# v0_2.net
KiCad netlist of a schematic drawn in EAGLE
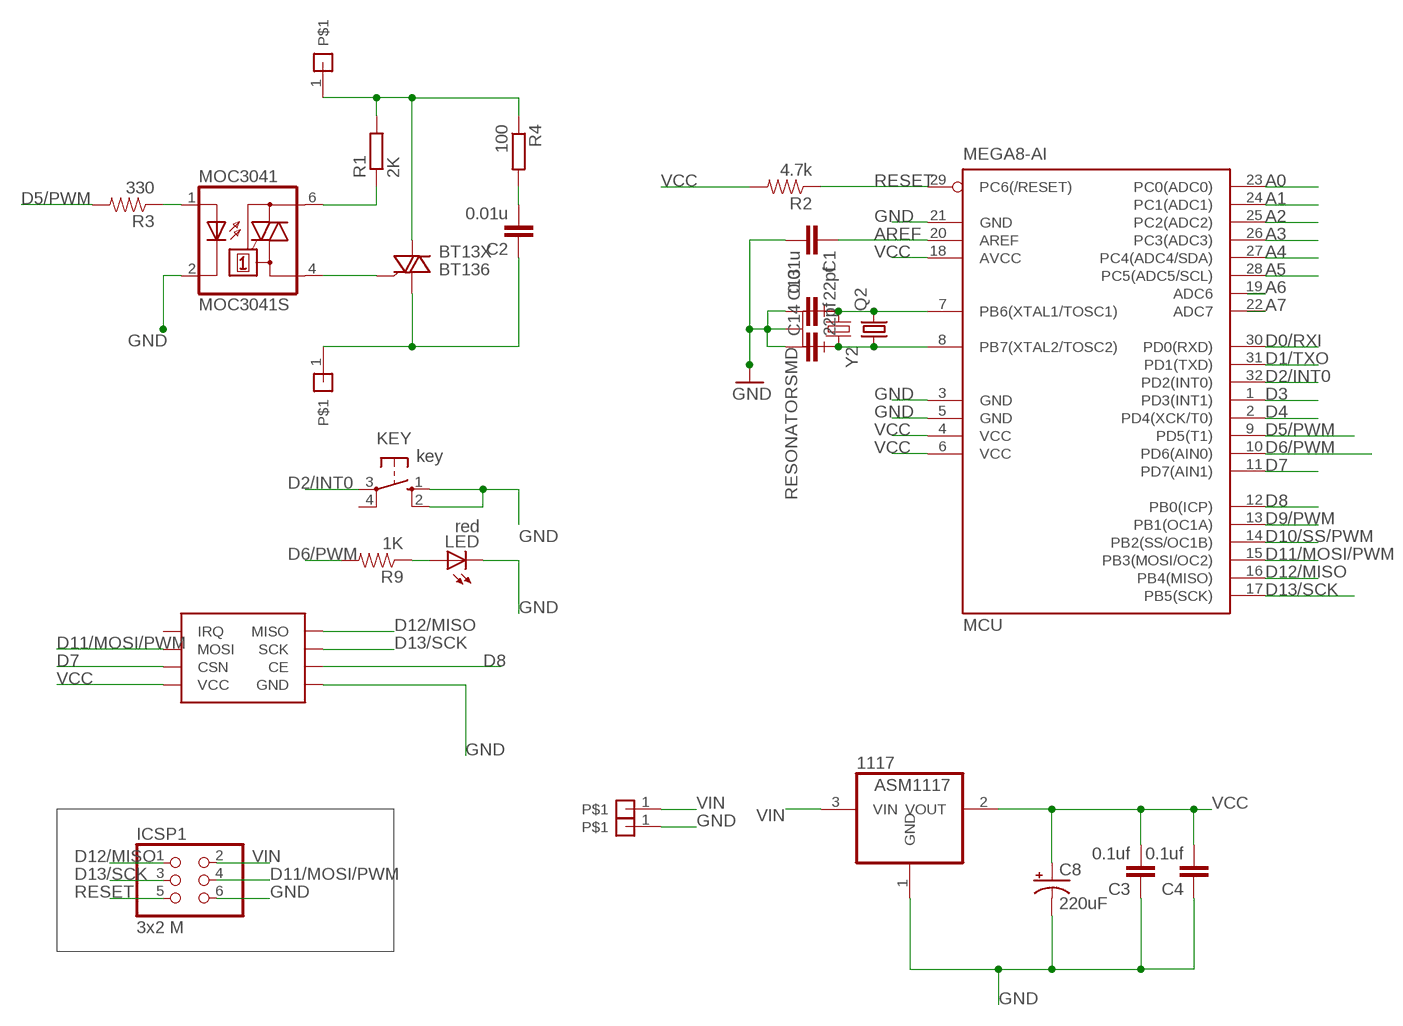
[diagram p0: schematic, sheet 1]

(export (version "E")
  (design (tool "Eeschema 10.0.6"))
  (components
    (comp (ref "1117")
      (value "ASM1117")
      (footprint "eagle-import:SOT223")
      (fields (field (name "MPN") "REG1117"))
      (libsource (lib "eagle-import") (part "REG1117"))
    )
    (comp (ref "BT13X")
      (value "BT136")
      (footprint "eagle-import:TO252")
      (libsource (lib "eagle-import") (part "BT136"))
    )
    (comp (ref "C1")
      (value "0.01u")
      (footprint "eagle-import:0603-CAP")
      (libsource (lib "eagle-import") (part "MY2_CAP0603-CAP"))
    )
    (comp (ref "C2")
      (value "0.01u")
      (footprint "eagle-import:C050-024X044")
      (libsource (lib "eagle-import") (part "C-EU050-024X044"))
    )
    (comp (ref "C3")
      (value "0.1uf")
      (footprint "eagle-import:0603-CAP")
      (libsource (lib "eagle-import") (part "MY_CAP0603-CAP"))
    )
    (comp (ref "C4")
      (value "0.1uf")
      (footprint "eagle-import:0603-CAP")
      (libsource (lib "eagle-import") (part "MY_CAP0603-CAP"))
    )
    (comp (ref "C8")
      (value "220uF")
      (footprint "eagle-import:EIA3528")
      (libsource (lib "eagle-import") (part "CAP_POL3528"))
    )
    (comp (ref "C13")
      (value "22pf")
      (footprint "eagle-import:0603-CAP")
      (libsource (lib "eagle-import") (part "CAP0603-CAP"))
    )
    (comp (ref "C14")
      (value "22pf")
      (footprint "eagle-import:0603-CAP")
      (libsource (lib "eagle-import") (part "CAP0603-CAP"))
    )
    (comp (ref "ICSP1")
      (value "3x2 M")
      (footprint "eagle-import:2X03")
      (libsource (lib "eagle-import") (part "PINHD-2X3"))
    )
    (comp (ref "KEY")
      (value "key")
      (footprint "eagle-import:B3F-10XX")
      (fields
        (field (name "MPN") "B3F-1000")
        (field (name "MPN_1") "B3F-1000")
        (field (name "OC_FARNELL") "176432")
        (field (name "OC_NEWARK") "36M3542")
      )
      (libsource (lib "eagle-import") (part "10-XX"))
    )
    (comp (ref "LED")
      (value "red")
      (footprint "eagle-import:LED3MM")
      (libsource (lib "eagle-import") (part "LED3MM"))
    )
    (comp (ref "MCU")
      (value "MEGA8-AI")
      (footprint "eagle-import:TQFP32-08")
      (fields (field (name "MPN") "ATMEGA8-16AU"))
      (libsource (lib "eagle-import") (part "MEGA8-AI"))
    )
    (comp (ref "MOC3041")
      (value "MOC3041S")
      (footprint "eagle-import:DIL6-SMD")
      (fields
        (field (name "MF") "FAIRCHILD SEMICONDUCTOR")
        (field (name "MPN") "MOC3041S-M")
        (field (name "MF_1") "FAIRCHILD SEMICONDUCTOR")
        (field (name "MPN_1") "MOC3041S-M")
        (field (name "OC_NEWARK") "05C2885")
      )
      (libsource (lib "eagle-import") (part "MOC30S41"))
    )
    (comp (ref "Q2")
      (value "CRYSTALHC49S")
      (footprint "eagle-import:HC49_S")
      (libsource (lib "eagle-import") (part "CRYSTALHC49S"))
    )
    (comp (ref "R1")
      (value "2K")
      (footprint "eagle-import:0204_7")
      (libsource (lib "eagle-import") (part "R-EU_0204/7"))
    )
    (comp (ref "R2")
      (value "4.7k")
      (footprint "eagle-import:0603-RES")
      (libsource (lib "eagle-import") (part "RESISTOR0603-RES"))
    )
    (comp (ref "R3")
      (value "330")
      (footprint "eagle-import:0603-RES")
      (libsource (lib "eagle-import") (part "RESISTOR0603-RES"))
    )
    (comp (ref "R4")
      (value "100")
      (footprint "eagle-import:0204_7")
      (libsource (lib "eagle-import") (part "R-EU_0204/7"))
    )
    (comp (ref "R9")
      (value "1K")
      (footprint "eagle-import:0603-RES")
      (libsource (lib "eagle-import") (part "RESISTOR0603-RES"))
    )
    (comp (ref "U$1")
      (value "PIN1")
      (footprint "eagle-import:PIN1")
      (libsource (lib "eagle-import") (part "PIN1"))
    )
    (comp (ref "U$2")
      (value "PIN1")
      (footprint "eagle-import:PIN1")
      (libsource (lib "eagle-import") (part "PIN1"))
    )
    (comp (ref "U$3")
      (value "PIN1")
      (footprint "eagle-import:PIN1")
      (libsource (lib "eagle-import") (part "PIN1"))
    )
    (comp (ref "U$4")
      (value "PIN1")
      (footprint "eagle-import:PIN1")
      (libsource (lib "eagle-import") (part "PIN1"))
    )
    (comp (ref "U$6")
      (value "NRF")
      (footprint "eagle-import:NRF")
      (libsource (lib "eagle-import") (part "NRF"))
    )
    (comp (ref "Y2")
      (value "RESONATORSMD")
      (footprint "eagle-import:RESONATOR-SMD")
      (libsource (lib "eagle-import") (part "RESONATORSMD"))
    )
  )
  (nets
    (net (code "1") (name "/A0") (class "Default")
      (node (ref "MCU") (pin "23") (pinfunction "PC0(ADC0)_23") (pintype "bidirectional"))
    )
    (net (code "2") (name "/A1") (class "Default")
      (node (ref "MCU") (pin "24") (pinfunction "PC1(ADC1)_24") (pintype "bidirectional"))
    )
    (net (code "3") (name "/A2") (class "Default")
      (node (ref "MCU") (pin "25") (pinfunction "PC2(ADC2)_25") (pintype "bidirectional"))
    )
    (net (code "4") (name "/A3") (class "Default")
      (node (ref "MCU") (pin "26") (pinfunction "PC3(ADC3)_26") (pintype "bidirectional"))
    )
    (net (code "5") (name "/A4") (class "Default")
      (node (ref "MCU") (pin "27") (pinfunction "PC4(ADC4/SDA)_27") (pintype "bidirectional"))
    )
    (net (code "6") (name "/A5") (class "Default")
      (node (ref "MCU") (pin "28") (pinfunction "PC5(ADC5/SCL)_28") (pintype "bidirectional"))
    )
    (net (code "7") (name "/A6") (class "Default")
      (node (ref "MCU") (pin "19") (pinfunction "ADC6_19") (pintype "bidirectional"))
    )
    (net (code "8") (name "/A7") (class "Default")
      (node (ref "MCU") (pin "22") (pinfunction "ADC7_22") (pintype "bidirectional"))
    )
    (net (code "9") (name "/AREF") (class "Default")
      (node (ref "C1") (pin "1") (pinfunction "1_1") (pintype "passive"))
      (node (ref "MCU") (pin "20") (pinfunction "AREF_20") (pintype "passive"))
    )
    (net (code "10") (name "/D0{slash}RXI") (class "Default")
      (node (ref "MCU") (pin "30") (pinfunction "PD0(RXD)_30") (pintype "bidirectional"))
    )
    (net (code "11") (name "/D1{slash}TXO") (class "Default")
      (node (ref "MCU") (pin "31") (pinfunction "PD1(TXD)_31") (pintype "bidirectional"))
    )
    (net (code "12") (name "/D2{slash}INT0") (class "Default")
      (node (ref "KEY") (pin "3") (pinfunction "P_3") (pintype "passive"))
      (node (ref "MCU") (pin "32") (pinfunction "PD2(INT0)_32") (pintype "bidirectional"))
    )
    (net (code "13") (name "/D3") (class "Default")
      (node (ref "MCU") (pin "1") (pinfunction "PD3(INT1)_1") (pintype "bidirectional"))
    )
    (net (code "14") (name "/D4") (class "Default")
      (node (ref "MCU") (pin "2") (pinfunction "PD4(XCK/T0)_2") (pintype "bidirectional"))
    )
    (net (code "15") (name "/D5{slash}PWM") (class "Default")
      (node (ref "MCU") (pin "9") (pinfunction "PD5(T1)_9") (pintype "bidirectional"))
      (node (ref "R3") (pin "2") (pinfunction "2_2") (pintype "passive"))
    )
    (net (code "16") (name "/D6{slash}PWM") (class "Default")
      (node (ref "MCU") (pin "10") (pinfunction "PD6(AIN0)_10") (pintype "bidirectional"))
      (node (ref "R9") (pin "2") (pinfunction "2_2") (pintype "passive"))
    )
    (net (code "17") (name "/D7") (class "Default")
      (node (ref "MCU") (pin "11") (pinfunction "PD7(AIN1)_11") (pintype "bidirectional"))
      (node (ref "U$6") (pin "P$4") (pinfunction "CSN_P$4") (pintype "bidirectional"))
    )
    (net (code "18") (name "/D8") (class "Default")
      (node (ref "MCU") (pin "12") (pinfunction "PB0(ICP)_12") (pintype "bidirectional"))
      (node (ref "U$6") (pin "P$3") (pinfunction "CE_P$3") (pintype "bidirectional"))
    )
    (net (code "19") (name "/D9{slash}PWM") (class "Default")
      (node (ref "MCU") (pin "13") (pinfunction "PB1(OC1A)_13") (pintype "bidirectional"))
    )
    (net (code "20") (name "/D10{slash}SS{slash}PWM") (class "Default")
      (node (ref "MCU") (pin "14") (pinfunction "PB2(SS/OC1B)_14") (pintype "bidirectional"))
    )
    (net (code "21") (name "/D11{slash}MOSI{slash}PWM") (class "Default")
      (node (ref "ICSP1") (pin "4") (pinfunction "4_4") (pintype "passive"))
      (node (ref "MCU") (pin "15") (pinfunction "PB3(MOSI/OC2)_15") (pintype "bidirectional"))
      (node (ref "U$6") (pin "P$6") (pinfunction "MOSI_P$6") (pintype "bidirectional"))
    )
    (net (code "22") (name "/D12{slash}MISO") (class "Default")
      (node (ref "ICSP1") (pin "1") (pinfunction "1_1") (pintype "passive"))
      (node (ref "MCU") (pin "16") (pinfunction "PB4(MISO)_16") (pintype "bidirectional"))
      (node (ref "U$6") (pin "P$7") (pinfunction "MISO_P$7") (pintype "bidirectional"))
    )
    (net (code "23") (name "/D13{slash}SCK") (class "Default")
      (node (ref "ICSP1") (pin "3") (pinfunction "3_3") (pintype "passive"))
      (node (ref "MCU") (pin "17") (pinfunction "PB5(SCK)_17") (pintype "bidirectional"))
      (node (ref "U$6") (pin "P$5") (pinfunction "SCK_P$5") (pintype "bidirectional"))
    )
    (net (code "24") (name "/RESET") (class "Default")
      (node (ref "ICSP1") (pin "5") (pinfunction "5_5") (pintype "passive"))
      (node (ref "MCU") (pin "29") (pinfunction "PC6(/RESET)_29") (pintype "bidirectional"))
      (node (ref "R2") (pin "1") (pinfunction "1_1") (pintype "passive"))
    )
    (net (code "25") (name "/VCC") (class "Default")
      (node (ref "1117") (pin "2") (pinfunction "VOUT_2") (pintype "output"))
      (node (ref "C3") (pin "2") (pinfunction "2_2") (pintype "passive"))
      (node (ref "C4") (pin "2") (pinfunction "2_2") (pintype "passive"))
      (node (ref "C8") (pin "A") (pinfunction "+_A") (pintype "passive"))
      (node (ref "MCU") (pin "18") (pinfunction "AVCC_18") (pintype "power_in"))
      (node (ref "MCU") (pin "4") (pinfunction "VCC_4") (pintype "power_in"))
      (node (ref "MCU") (pin "6") (pinfunction "VCC_6") (pintype "power_in"))
      (node (ref "R2") (pin "2") (pinfunction "2_2") (pintype "passive"))
      (node (ref "U$6") (pin "P$2") (pinfunction "VCC_P$2") (pintype "bidirectional"))
    )
    (net (code "26") (name "/VIN") (class "Default")
      (node (ref "1117") (pin "3") (pinfunction "VIN_3") (pintype "input"))
      (node (ref "ICSP1") (pin "2") (pinfunction "2_2") (pintype "passive"))
      (node (ref "U$3") (pin "1") (pinfunction "P$1_1") (pintype "bidirectional"))
    )
    (net (code "27") (name "GND") (class "Default")
      (node (ref "1117") (pin "1") (pinfunction "GND_1") (pintype "power_in"))
      (node (ref "C1") (pin "2") (pinfunction "2_2") (pintype "passive"))
      (node (ref "C13") (pin "1") (pinfunction "1_1") (pintype "passive"))
      (node (ref "C14") (pin "1") (pinfunction "1_1") (pintype "passive"))
      (node (ref "C3") (pin "1") (pinfunction "1_1") (pintype "passive"))
      (node (ref "C4") (pin "1") (pinfunction "1_1") (pintype "passive"))
      (node (ref "C8") (pin "C") (pinfunction "-_C") (pintype "passive"))
      (node (ref "ICSP1") (pin "6") (pinfunction "6_6") (pintype "passive"))
      (node (ref "KEY") (pin "1") (pinfunction "S_1") (pintype "passive"))
      (node (ref "KEY") (pin "2") (pinfunction "S1_2") (pintype "passive"))
      (node (ref "LED") (pin "K") (pinfunction "C_K") (pintype "passive"))
      (node (ref "MCU") (pin "21") (pinfunction "GND_21") (pintype "power_in"))
      (node (ref "MCU") (pin "3") (pinfunction "GND_3") (pintype "power_in"))
      (node (ref "MCU") (pin "5") (pinfunction "GND_5") (pintype "power_in"))
      (node (ref "MOC3041") (pin "2") (pinfunction "C_2") (pintype "passive"))
      (node (ref "U$4") (pin "1") (pinfunction "P$1_1") (pintype "bidirectional"))
      (node (ref "U$6") (pin "P$1") (pinfunction "GND_P$1") (pintype "bidirectional"))
      (node (ref "Y2") (pin "2") (pinfunction "2_2") (pintype "passive"))
    )
    (net (code "28") (name "Net-(BT13X-A1)") (class "Default")
      (node (ref "BT13X") (pin "1") (pinfunction "A1_1") (pintype "passive"))
      (node (ref "C2") (pin "1") (pinfunction "1_1") (pintype "passive"))
      (node (ref "U$1") (pin "1") (pinfunction "P$1_1") (pintype "bidirectional"))
    )
    (net (code "29") (name "Net-(BT13X-A2)") (class "Default")
      (node (ref "BT13X") (pin "3") (pinfunction "A2_3") (pintype "passive"))
      (node (ref "R1") (pin "2") (pinfunction "2_2") (pintype "passive"))
      (node (ref "R4") (pin "1") (pinfunction "1_1") (pintype "passive"))
      (node (ref "U$2") (pin "1") (pinfunction "P$1_1") (pintype "bidirectional"))
    )
    (net (code "30") (name "Net-(BT13X-G)") (class "Default")
      (node (ref "BT13X") (pin "2") (pinfunction "G_2") (pintype "passive"))
      (node (ref "MOC3041") (pin "4") (pinfunction "A1_4") (pintype "passive"))
    )
    (net (code "31") (name "Net-(C2-Pad2)") (class "Default")
      (node (ref "C2") (pin "2") (pinfunction "2_2") (pintype "passive"))
      (node (ref "R4") (pin "2") (pinfunction "2_2") (pintype "passive"))
    )
    (net (code "32") (name "Net-(LED-PadA)") (class "Default")
      (node (ref "LED") (pin "A") (pinfunction "A_A") (pintype "passive"))
      (node (ref "R9") (pin "1") (pinfunction "1_1") (pintype "passive"))
    )
    (net (code "33") (name "Net-(MCU-PB6(XTAL1{slash}TOSC1))") (class "Default")
      (node (ref "C13") (pin "2") (pinfunction "2_2") (pintype "passive"))
      (node (ref "MCU") (pin "7") (pinfunction "PB6(XTAL1/TOSC1)_7") (pintype "bidirectional"))
      (node (ref "Q2") (pin "2") (pinfunction "2_2") (pintype "passive"))
      (node (ref "Y2") (pin "1") (pinfunction "1_1") (pintype "passive"))
    )
    (net (code "34") (name "Net-(MCU-PB7(XTAL2{slash}TOSC2))") (class "Default")
      (node (ref "C14") (pin "2") (pinfunction "2_2") (pintype "passive"))
      (node (ref "MCU") (pin "8") (pinfunction "PB7(XTAL2/TOSC2)_8") (pintype "bidirectional"))
      (node (ref "Q2") (pin "1") (pinfunction "1_1") (pintype "passive"))
      (node (ref "Y2") (pin "3") (pinfunction "3_3") (pintype "passive"))
    )
    (net (code "35") (name "Net-(MOC3041-A)") (class "Default")
      (node (ref "MOC3041") (pin "1") (pinfunction "A_1") (pintype "passive"))
      (node (ref "R3") (pin "1") (pinfunction "1_1") (pintype "passive"))
    )
    (net (code "36") (name "Net-(MOC3041-A2)") (class "Default")
      (node (ref "MOC3041") (pin "6") (pinfunction "A2_6") (pintype "passive"))
      (node (ref "R1") (pin "1") (pinfunction "1_1") (pintype "passive"))
    )
    (net (code "37") (name "unconnected-(KEY-P1-Pad4)") (class "Default")
      (node (ref "KEY") (pin "4") (pinfunction "P1_4") (pintype "passive"))
    )
    (net (code "38") (name "unconnected-(U$6-IRQ-PadP$8)") (class "Default")
      (node (ref "U$6") (pin "P$8") (pinfunction "IRQ_P$8") (pintype "bidirectional"))
    )
  )
)
